# Headers_and_Breakaways.net
KiCad netlist of a schematic drawn in Altium Designer
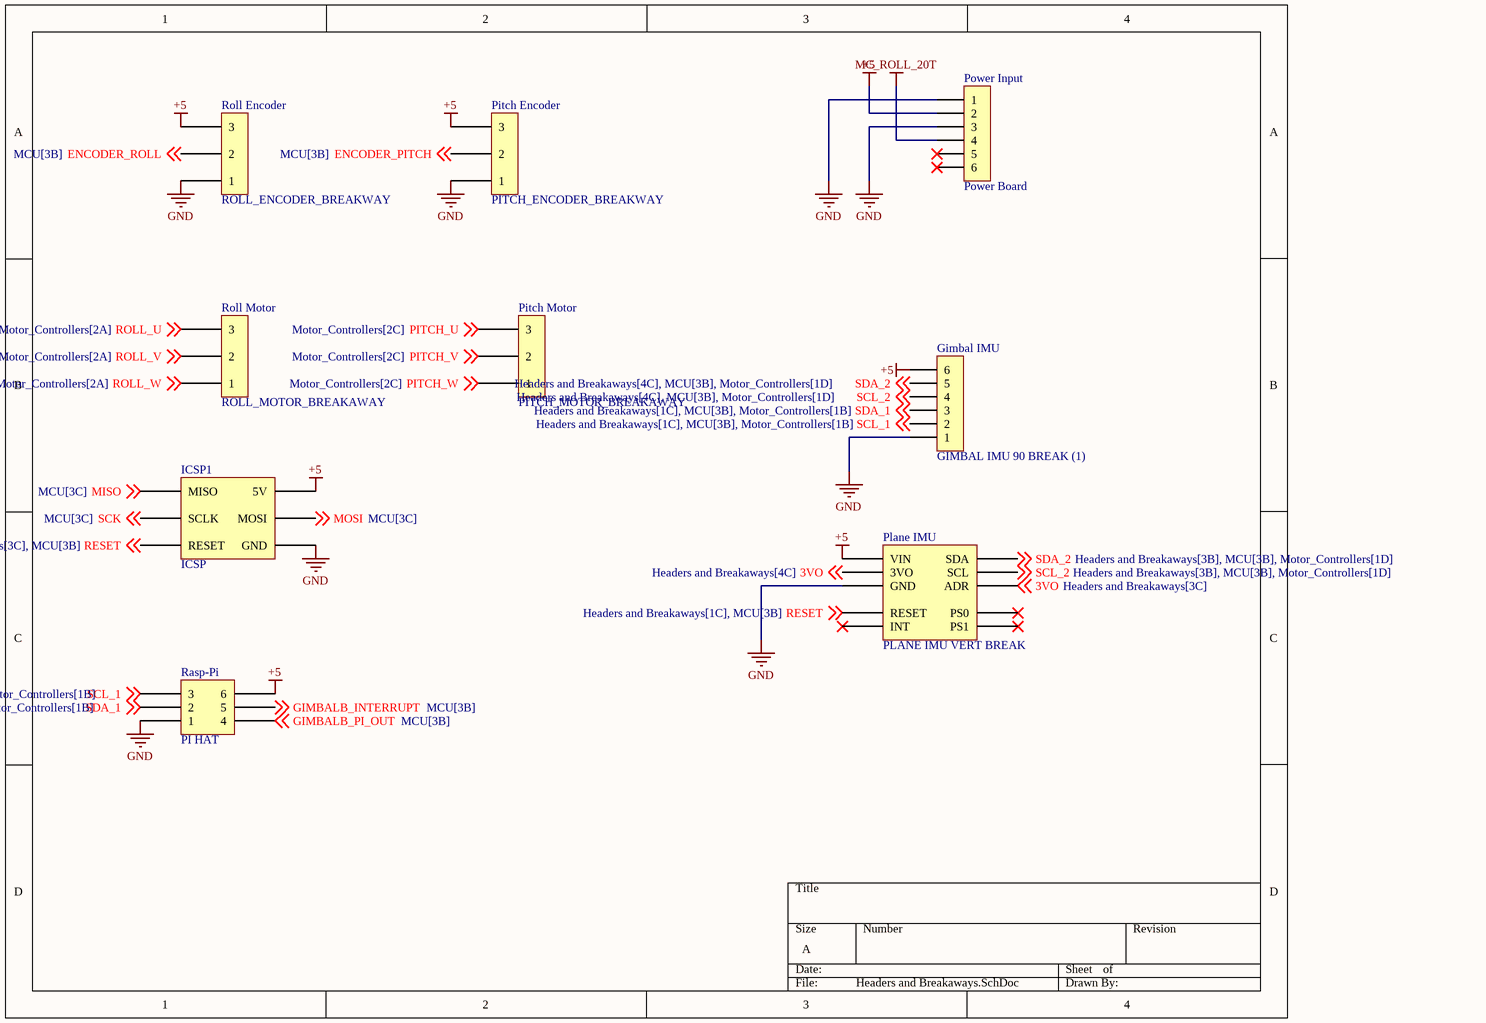
[diagram p0: Headers and Breakaways.SchDoc]

(export (version "E")
  (design (tool "Eeschema 10.0.6"))
  (components
    (comp (ref "Gimbal IMU")
      (value "GIMBAL IMU 90 BREAK (1)")
      (footprint "Molex Microfit 3.0 1x6 Right Angle")
      (fields (field (name "MF") "Molex") (field (name "MP") "43650-0600"))
      (libsource (lib "Molex Microfit Schematic Lib") (part "Molex Microfit 3.0 1x6 Right Angle"))
    )
    (comp (ref "ICSP1")
      (value "ICSP")
      (footprint "2x3 Breakaway Vertical")
      (libsource (lib "2.54mm Pitch Breakaway Schematic Lib") (part "ICSP"))
    )
    (comp (ref "Pitch Encoder")
      (value "PITCH_ENCODER_BREAKWAY")
      (footprint "1x3 Breakaway Right Angle")
      (fields (field (name "MPN") "5-104935-3") (field (name "MANUFACTURER") "TE"))
      (libsource (lib "2.54mm Pitch Breakaway Schematic Lib") (part "1x3 Right Angle Breakaway"))
    )
    (comp (ref "Pitch Motor")
      (value "PITCH_MOTOR_BREAKAWAY")
      (footprint "1x3 Breakaway Right Angle")
      (fields (field (name "MPN") "5-104935-3") (field (name "MANUFACTURER") "TE"))
      (libsource (lib "2.54mm Pitch Breakaway Schematic Lib") (part "1x3 Right Angle Breakaway"))
    )
    (comp (ref "Plane IMU")
      (value "PLANE IMU VERT BREAK")
      (footprint "BNO055 Breakout")
      (description "Adafruit BNO055 Breakout Board Mount FRONT SIDE UP")
      (fields (field (name "MPN") "2472") (field (name "MANUFACTURER") "Adafruit"))
      (libsource (lib "Common ICs Schematic Lib") (part "BNO055 Breakout"))
    )
    (comp (ref "Power Input")
      (value "Power Board")
      (footprint "Molex Microfit 3.0 1x6 Right Angle")
      (fields (field (name "MF") "Molex") (field (name "MP") "43650-0600"))
      (libsource (lib "") (part "Molex Microfit 3.0 1x6 Right Angle_1"))
    )
    (comp (ref "Rasp-Pi")
      (value "PI HAT")
      (footprint "Molex Microfit 3.0 2x3 Right Angle")
      (fields (field (name "MPN") "0430450601"))
      (libsource (lib "Molex Microfit Schematic Lib") (part "Molex Microfit 3.0 2x3 Right Angle"))
    )
    (comp (ref "Roll Encoder")
      (value "ROLL_ENCODER_BREAKWAY")
      (footprint "1x3 Breakaway Right Angle")
      (fields (field (name "MPN") "5-104935-3") (field (name "MANUFACTURER") "TE"))
      (libsource (lib "2.54mm Pitch Breakaway Schematic Lib") (part "1x3 Right Angle Breakaway"))
    )
    (comp (ref "Roll Motor")
      (value "ROLL_MOTOR_BREAKAWAY")
      (footprint "1x3 Breakaway Right Angle")
      (fields (field (name "MPN") "5-104935-3") (field (name "MANUFACTURER") "TE"))
      (libsource (lib "2.54mm Pitch Breakaway Schematic Lib") (part "1x3 Right Angle Breakaway"))
    )
  )
  (nets
    (net (code "1") (name "+5") (class "Default")
      (node (ref "Gimbal IMU") (pin "6") (pinfunction "6_6") (pintype "passive"))
      (node (ref "ICSP1") (pin "6") (pinfunction "5V_6") (pintype "passive"))
      (node (ref "Pitch Encoder") (pin "3") (pinfunction "3_3") (pintype "passive"))
      (node (ref "Plane IMU") (pin "6") (pinfunction "VIN_6") (pintype "passive"))
      (node (ref "Power Input") (pin "2") (pinfunction "2_2") (pintype "passive"))
      (node (ref "Rasp-Pi") (pin "6") (pinfunction "6_6") (pintype "passive"))
      (node (ref "Roll Encoder") (pin "3") (pinfunction "3_3") (pintype "passive"))
    )
    (net (code "2") (name "3VO") (class "Default")
      (node (ref "Plane IMU") (pin "5") (pinfunction "3VO_5") (pintype "passive"))
      (node (ref "Plane IMU") (pin "7") (pinfunction "ADR_7") (pintype "passive"))
    )
    (net (code "3") (name "ENCODER_PITCH") (class "Default")
      (node (ref "Pitch Encoder") (pin "2") (pinfunction "2_2") (pintype "passive"))
    )
    (net (code "4") (name "ENCODER_ROLL") (class "Default")
      (node (ref "Roll Encoder") (pin "2") (pinfunction "2_2") (pintype "passive"))
    )
    (net (code "5") (name "GIMBALB_INTERRUPT") (class "Default")
      (node (ref "Rasp-Pi") (pin "5") (pinfunction "5_5") (pintype "passive"))
    )
    (net (code "6") (name "GIMBALB_PI_OUT") (class "Default")
      (node (ref "Rasp-Pi") (pin "4") (pinfunction "4_4") (pintype "passive"))
    )
    (net (code "7") (name "GND") (class "Default")
      (node (ref "Gimbal IMU") (pin "1") (pinfunction "1_1") (pintype "passive"))
      (node (ref "ICSP1") (pin "4") (pinfunction "GND_4") (pintype "passive"))
      (node (ref "Pitch Encoder") (pin "1") (pinfunction "1_1") (pintype "passive"))
      (node (ref "Plane IMU") (pin "4") (pinfunction "GND_4") (pintype "passive"))
      (node (ref "Power Input") (pin "1") (pinfunction "1_1") (pintype "passive"))
      (node (ref "Power Input") (pin "3") (pinfunction "3_3") (pintype "passive"))
      (node (ref "Rasp-Pi") (pin "1") (pinfunction "1_1") (pintype "passive"))
      (node (ref "Roll Encoder") (pin "1") (pinfunction "1_1") (pintype "passive"))
    )
    (net (code "8") (name "MC_ROLL_20T") (class "Default")
      (node (ref "Power Input") (pin "4") (pinfunction "4_4") (pintype "passive"))
    )
    (net (code "9") (name "MISO") (class "Default")
      (node (ref "ICSP1") (pin "3") (pinfunction "MISO_3") (pintype "passive"))
    )
    (net (code "10") (name "MOSI") (class "Default")
      (node (ref "ICSP1") (pin "5") (pinfunction "MOSI_5") (pintype "passive"))
    )
    (net (code "11") (name "PITCH_U") (class "Default")
      (node (ref "Pitch Motor") (pin "3") (pinfunction "3_3") (pintype "passive"))
    )
    (net (code "12") (name "PITCH_V") (class "Default")
      (node (ref "Pitch Motor") (pin "2") (pinfunction "2_2") (pintype "passive"))
    )
    (net (code "13") (name "PITCH_W") (class "Default")
      (node (ref "Pitch Motor") (pin "1") (pinfunction "1_1") (pintype "passive"))
    )
    (net (code "14") (name "RESET") (class "Default")
      (node (ref "ICSP1") (pin "1") (pinfunction "RESET_1") (pintype "passive"))
      (node (ref "Plane IMU") (pin "1") (pinfunction "RESET_1") (pintype "passive"))
    )
    (net (code "15") (name "ROLL_U") (class "Default")
      (node (ref "Roll Motor") (pin "3") (pinfunction "3_3") (pintype "passive"))
    )
    (net (code "16") (name "ROLL_V") (class "Default")
      (node (ref "Roll Motor") (pin "2") (pinfunction "2_2") (pintype "passive"))
    )
    (net (code "17") (name "ROLL_W") (class "Default")
      (node (ref "Roll Motor") (pin "1") (pinfunction "1_1") (pintype "passive"))
    )
    (net (code "18") (name "SCK") (class "Default")
      (node (ref "ICSP1") (pin "2") (pinfunction "SCLK_2") (pintype "passive"))
    )
    (net (code "19") (name "SCL_1") (class "Default")
      (node (ref "Gimbal IMU") (pin "2") (pinfunction "2_2") (pintype "passive"))
      (node (ref "Rasp-Pi") (pin "3") (pinfunction "3_3") (pintype "passive"))
    )
    (net (code "20") (name "SCL_2") (class "Default")
      (node (ref "Gimbal IMU") (pin "4") (pinfunction "4_4") (pintype "passive"))
      (node (ref "Plane IMU") (pin "2") (pinfunction "SCL_2") (pintype "passive"))
    )
    (net (code "21") (name "SDA_1") (class "Default")
      (node (ref "Gimbal IMU") (pin "3") (pinfunction "3_3") (pintype "passive"))
      (node (ref "Rasp-Pi") (pin "2") (pinfunction "2_2") (pintype "passive"))
    )
    (net (code "22") (name "SDA_2") (class "Default")
      (node (ref "Gimbal IMU") (pin "5") (pinfunction "5_5") (pintype "passive"))
      (node (ref "Plane IMU") (pin "3") (pinfunction "SDA_3") (pintype "passive"))
    )
    (net (code "23") (name "unconnected-(Plane IMU-INT-Pad8)") (class "Default")
      (node (ref "Plane IMU") (pin "8") (pinfunction "INT_8") (pintype "passive+no_connect"))
    )
    (net (code "24") (name "unconnected-(Plane IMU-PS0-Pad10)") (class "Default")
      (node (ref "Plane IMU") (pin "10") (pinfunction "PS0_10") (pintype "passive+no_connect"))
    )
    (net (code "25") (name "unconnected-(Plane IMU-PS1-Pad9)") (class "Default")
      (node (ref "Plane IMU") (pin "9") (pinfunction "PS1_9") (pintype "passive+no_connect"))
    )
    (net (code "26") (name "unconnected-(Power Input-Pad5)") (class "Default")
      (node (ref "Power Input") (pin "5") (pinfunction "5_5") (pintype "passive+no_connect"))
    )
    (net (code "27") (name "unconnected-(Power Input-Pad6)") (class "Default")
      (node (ref "Power Input") (pin "6") (pinfunction "6_6") (pintype "passive+no_connect"))
    )
  )
)
